# FIREFLIES_2032_LDR.net
KiCad netlist of a schematic drawn in EAGLE
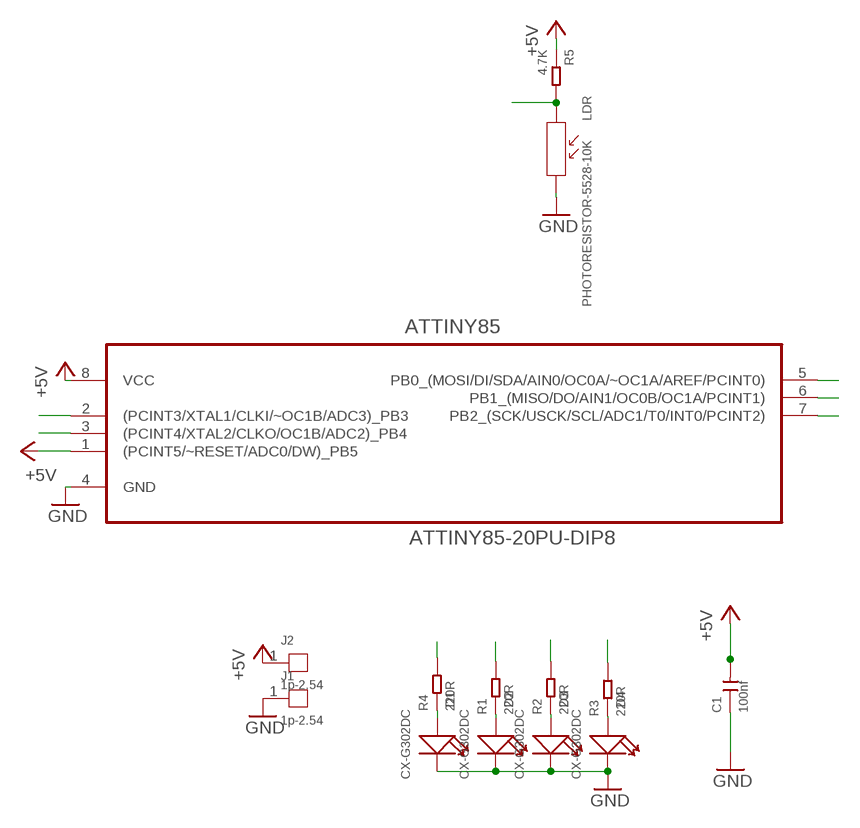
[diagram p0: schematic, sheet 1]

(export (version "E")
  (design (tool "Eeschema 10.0.6"))
  (components
    (comp (ref "ATTINY85")
      (value "ATTINY85-20PU-DIP8")
      (footprint "eagle-import:DIP254P762X533-8")
      (fields (field (name "MPN") "ATTINY85-20PU"))
      (libsource (lib "eagle-import") (part "MCU-ATTINY85-20PU(DIP8)1"))
    )
    (comp (ref "C1")
      (value "100nf")
      (footprint "eagle-import:CERAMIC-2.54")
      (fields (field (name "MPN") "CC1-F5SL2A101KSPW"))
      (libsource (lib "eagle-import") (part "DIP-CERAMIC-DISC-100NF-50V-Y5V(D5.0MM)"))
    )
    (comp (ref "D1")
      (value "CX-G302DC")
      (footprint "eagle-import:LED2-2.54-D3.0MM")
      (libsource (lib "eagle-import") (part "DIP-LED-GREEN-GREEN(2P-D3MM)"))
    )
    (comp (ref "D2")
      (value "CX-G302DC")
      (footprint "eagle-import:LED2-2.54-D3.0MM")
      (libsource (lib "eagle-import") (part "DIP-LED-GREEN-GREEN(2P-D3MM)"))
    )
    (comp (ref "D3")
      (value "CX-G302DC")
      (footprint "eagle-import:LED2-2.54-D3.0MM")
      (libsource (lib "eagle-import") (part "DIP-LED-GREEN-GREEN(2P-D3MM)"))
    )
    (comp (ref "D4")
      (value "CX-G302DC")
      (footprint "eagle-import:LED2-2.54-D3.0MM")
      (libsource (lib "eagle-import") (part "DIP-LED-GREEN-GREEN(2P-D3MM)"))
    )
    (comp (ref "J1")
      (value "1p-2.54")
      (footprint "eagle-import:1P-65_35MIL")
      (fields (field (name "MPN") "RF130-1013BBS0741"))
      (libsource (lib "eagle-import") (part "DIP-BLACK-ROUND-FEMALE-HEADER-VERT(1P-2.54)"))
    )
    (comp (ref "J2")
      (value "1p-2.54")
      (footprint "eagle-import:1P-65_35MIL")
      (fields (field (name "MPN") "RF130-1013BBS0741"))
      (libsource (lib "eagle-import") (part "DIP-BLACK-ROUND-FEMALE-HEADER-VERT(1P-2.54)"))
    )
    (comp (ref "LDR")
      (value "PHOTORESISTOR-5528-10K")
      (footprint "eagle-import:SNR2-3.0")
      (libsource (lib "eagle-import") (part "PHOTORESISTOR-5528-10K(2P-5.0X4.2MM)"))
    )
    (comp (ref "R1")
      (value "220R")
      (footprint "eagle-import:PR-D2.3XL6.5MM")
      (fields (field (name "MPN") "FHCFR-1/4W-221J"))
      (libsource (lib "eagle-import") (part "DIP-RES-220R-5%-1/4W(PR-D2.3XL6.5MM)"))
    )
    (comp (ref "R2")
      (value "220R")
      (footprint "eagle-import:PR-D2.3XL6.5MM")
      (fields (field (name "MPN") "FHCFR-1/4W-221J"))
      (libsource (lib "eagle-import") (part "DIP-RES-220R-5%-1/4W(PR-D2.3XL6.5MM)"))
    )
    (comp (ref "R3")
      (value "220R")
      (footprint "eagle-import:PR-D2.3XL6.5MM")
      (fields (field (name "MPN") "FHCFR-1/4W-221J"))
      (libsource (lib "eagle-import") (part "DIP-RES-220R-5%-1/4W(PR-D2.3XL6.5MM)"))
    )
    (comp (ref "R4")
      (value "220R")
      (footprint "eagle-import:PR-D2.3XL6.5MM")
      (fields (field (name "MPN") "FHCFR-1/4W-221J"))
      (libsource (lib "eagle-import") (part "DIP-RES-220R-5%-1/4W(PR-D2.3XL6.5MM)"))
    )
    (comp (ref "R5")
      (value "4.7K")
      (footprint "eagle-import:PR-D2.3XL6.5MM")
      (fields (field (name "MPN") "FHCFR-1/4W-472J"))
      (libsource (lib "eagle-import") (part "DIP-RES-4.7K-5%-1/4W(PR-D2.3XL6.5MM)"))
    )
  )
  (nets
    (net (code "1") (name "+5V") (class "Default")
      (node (ref "ATTINY85") (pin "1") (pinfunction "(PCINT5/~{RESET/ADC0/DW})_PB5_1") (pintype "bidirectional"))
      (node (ref "ATTINY85") (pin "8") (pinfunction "VCC_8") (pintype "power_in"))
      (node (ref "C1") (pin "2") (pinfunction "2_2") (pintype "passive"))
      (node (ref "J2") (pin "1") (pinfunction "1_1") (pintype "bidirectional"))
      (node (ref "R5") (pin "1") (pinfunction "1_1") (pintype "passive"))
    )
    (net (code "2") (name "/A1") (class "Default")
      (node (ref "ATTINY85") (pin "7") (pinfunction "PB2_(SCK/USCK/SCL/ADC1/T0/INT0/PCINT2)_7") (pintype "bidirectional"))
      (node (ref "LDR") (pin "1") (pinfunction "P$1_1") (pintype "bidirectional"))
      (node (ref "R5") (pin "2") (pinfunction "2_2") (pintype "passive"))
    )
    (net (code "3") (name "/A2") (class "Default")
      (node (ref "ATTINY85") (pin "3") (pinfunction "(PCINT4/XTAL2/CLKO/OC1B/ADC2)_PB4_3") (pintype "bidirectional"))
      (node (ref "R2") (pin "2") (pinfunction "2_2") (pintype "passive"))
    )
    (net (code "4") (name "/A3") (class "Default")
      (node (ref "ATTINY85") (pin "2") (pinfunction "(PCINT3/XTAL1/CLKI/~{OC1B/ADC3})_PB3_2") (pintype "bidirectional"))
      (node (ref "R1") (pin "2") (pinfunction "2_2") (pintype "passive"))
    )
    (net (code "5") (name "/D0") (class "Default")
      (node (ref "ATTINY85") (pin "5") (pinfunction "PB0_(MOSI/DI/SDA/AIN0/OC0A/~{OC1A/AREF/PCINT0})_5") (pintype "bidirectional"))
      (node (ref "R3") (pin "2") (pinfunction "2_2") (pintype "passive"))
    )
    (net (code "6") (name "/D1") (class "Default")
      (node (ref "ATTINY85") (pin "6") (pinfunction "PB1_(MISO/DO/AIN1/OC0B/OC1A/PCINT1)_6") (pintype "bidirectional"))
      (node (ref "R4") (pin "2") (pinfunction "2_2") (pintype "passive"))
    )
    (net (code "7") (name "GND") (class "Default")
      (node (ref "ATTINY85") (pin "4") (pinfunction "GND_4") (pintype "passive"))
      (node (ref "C1") (pin "1") (pinfunction "1_1") (pintype "passive"))
      (node (ref "D1") (pin "K") (pinfunction "-_K") (pintype "passive"))
      (node (ref "D2") (pin "K") (pinfunction "-_K") (pintype "passive"))
      (node (ref "D3") (pin "K") (pinfunction "-_K") (pintype "passive"))
      (node (ref "D4") (pin "K") (pinfunction "-_K") (pintype "passive"))
      (node (ref "J1") (pin "1") (pinfunction "1_1") (pintype "bidirectional"))
      (node (ref "LDR") (pin "2") (pinfunction "P$2_2") (pintype "bidirectional"))
    )
    (net (code "8") (name "Net-(D1-+)") (class "Default")
      (node (ref "D1") (pin "A") (pinfunction "+_A") (pintype "passive"))
      (node (ref "R4") (pin "1") (pinfunction "1_1") (pintype "passive"))
    )
    (net (code "9") (name "Net-(D2-+)") (class "Default")
      (node (ref "D2") (pin "A") (pinfunction "+_A") (pintype "passive"))
      (node (ref "R1") (pin "1") (pinfunction "1_1") (pintype "passive"))
    )
    (net (code "10") (name "Net-(D3-+)") (class "Default")
      (node (ref "D3") (pin "A") (pinfunction "+_A") (pintype "passive"))
      (node (ref "R2") (pin "1") (pinfunction "1_1") (pintype "passive"))
    )
    (net (code "11") (name "Net-(D4-+)") (class "Default")
      (node (ref "D4") (pin "A") (pinfunction "+_A") (pintype "passive"))
      (node (ref "R3") (pin "1") (pinfunction "1_1") (pintype "passive"))
    )
  )
)
